# pic16f1829_ads1232_ads1220_hx711.net
KiCad netlist of a schematic drawn in EAGLE
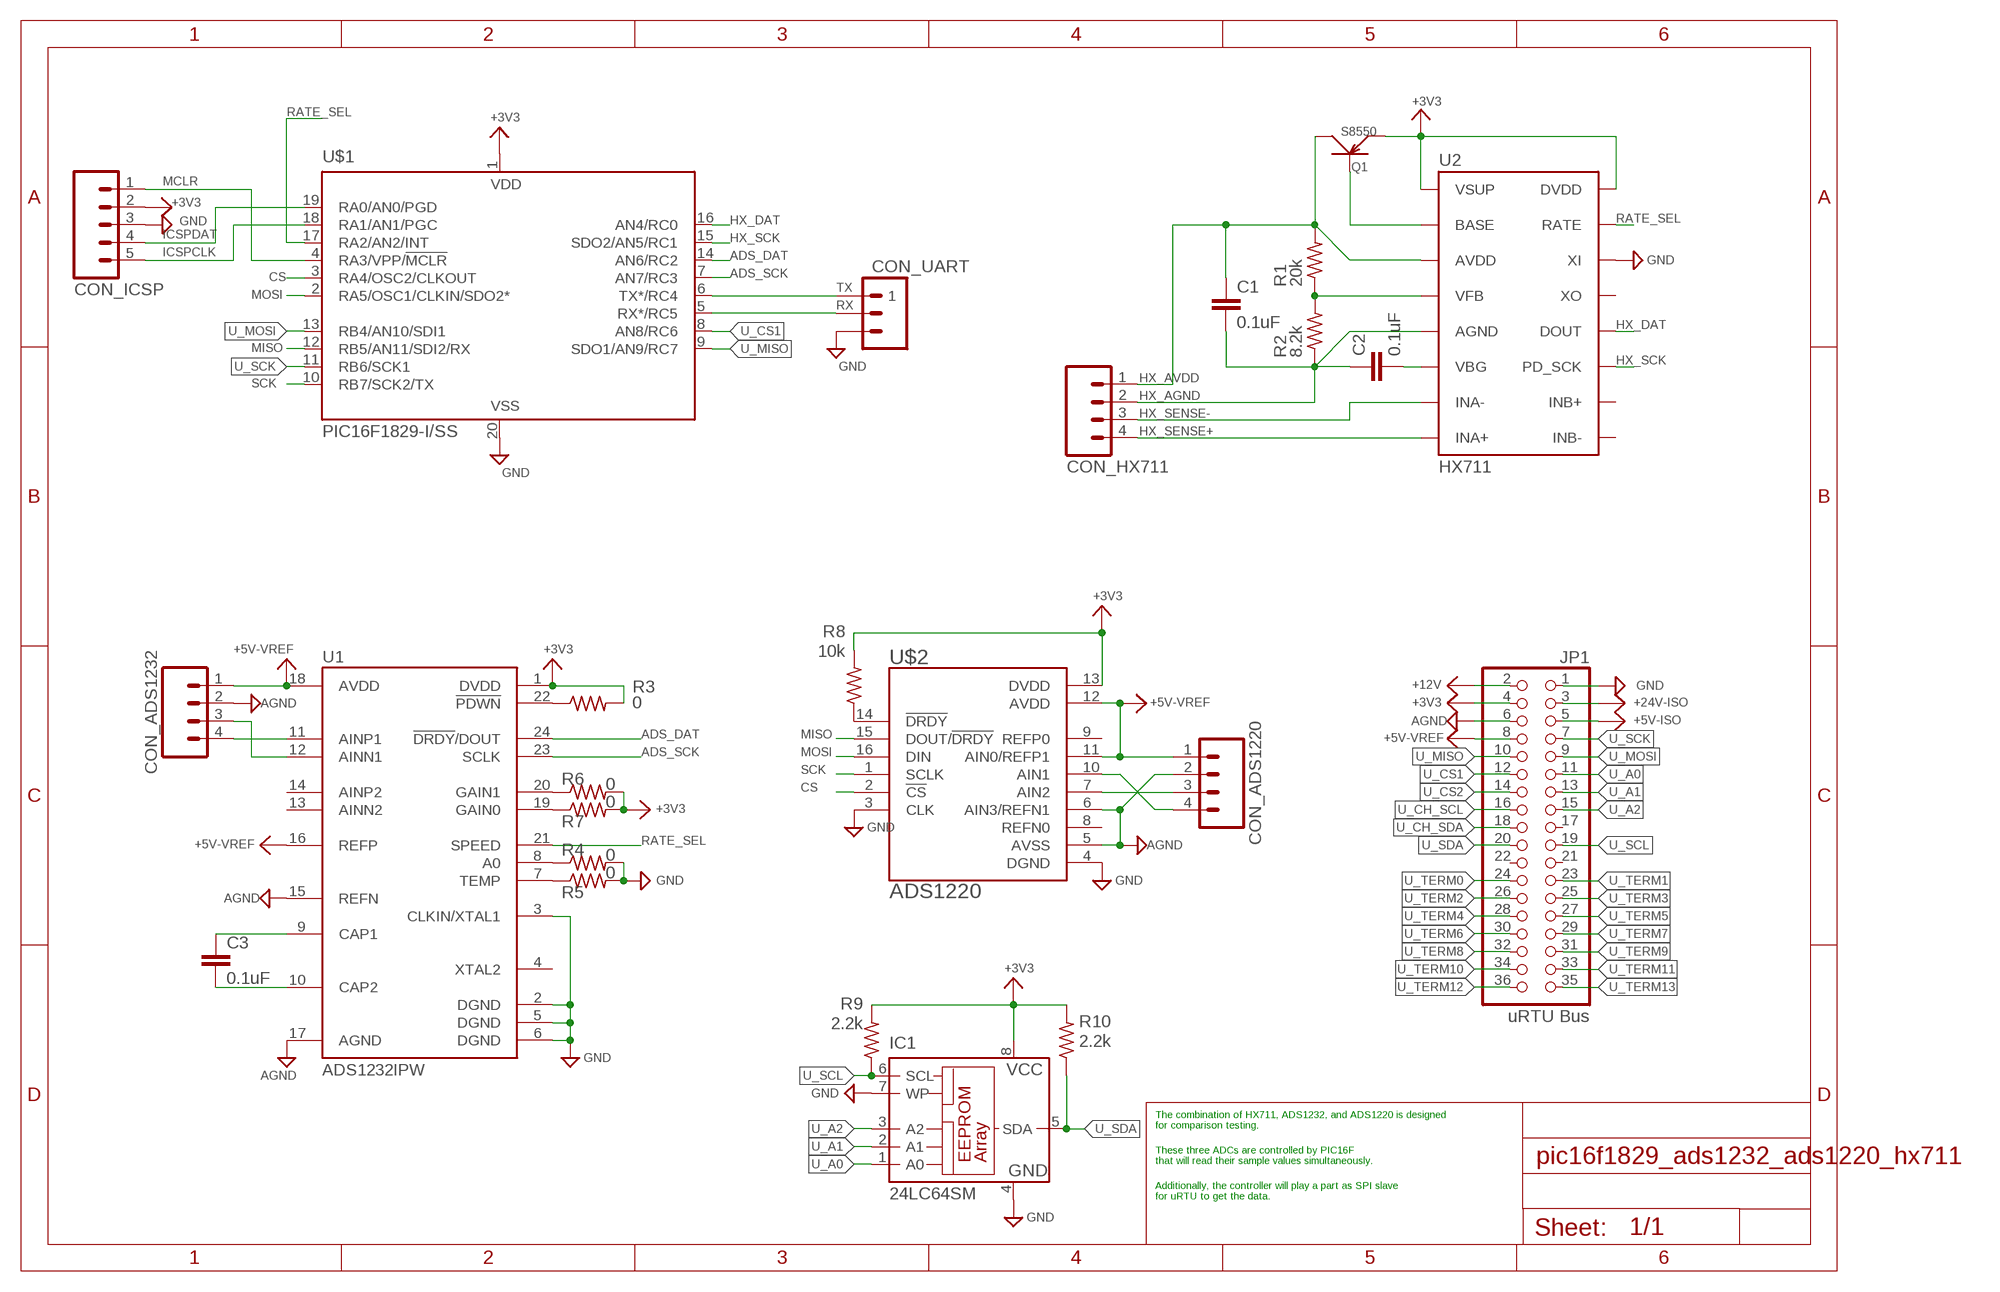
[diagram p0: schematic, sheet 1]

(export (version "E")
  (design (tool "Eeschema 10.0.6"))
  (components
    (comp (ref "C1")
      (value "0.1uF")
      (footprint "eagle-import:RCL_C0805")
      (libsource (lib "eagle-import") (part "RCL_C-EUC0805"))
    )
    (comp (ref "C2")
      (value "0.1uF")
      (footprint "eagle-import:RCL_C0805")
      (libsource (lib "eagle-import") (part "RCL_C-EUC0805"))
    )
    (comp (ref "C3")
      (value "0.1uF")
      (footprint "eagle-import:RCL_C0805")
      (libsource (lib "eagle-import") (part "RCL_C-EUC0805"))
    )
    (comp (ref "CON_ADS1220")
      (value "M04PTH")
      (footprint "eagle-import:1X04")
      (libsource (lib "eagle-import") (part "M04PTH"))
    )
    (comp (ref "CON_ADS1232")
      (value "M04PTH")
      (footprint "eagle-import:1X04")
      (libsource (lib "eagle-import") (part "M04PTH"))
    )
    (comp (ref "CON_HX711")
      (value "M04PTH")
      (footprint "eagle-import:1X04")
      (libsource (lib "eagle-import") (part "M04PTH"))
    )
    (comp (ref "CON_ICSP")
      (value "M05")
      (footprint "eagle-import:1X05")
      (libsource (lib "eagle-import") (part "M05"))
    )
    (comp (ref "CON_UART")
      (value "M03")
      (footprint "eagle-import:1X03")
      (libsource (lib "eagle-import") (part "M03"))
    )
    (comp (ref "IC1")
      (value "24LC64SM")
      (footprint "eagle-import:SO-08M")
      (fields (field (name "MF") "MICROCHIP") (field (name "MPN") "24LC64T-I/SN"))
      (libsource (lib "eagle-import") (part "24SMLC64"))
    )
    (comp (ref "JP1")
      (value "uRTU Bus")
      (footprint "eagle-import:2X18")
      (libsource (lib "eagle-import") (part "PINHD-2X18"))
    )
    (comp (ref "Q1")
      (value "S8550")
      (footprint "eagle-import:SOT-23")
      (libsource (lib "eagle-import") (part "SMD-TRANSISTORS-PNP-25V-500MA-S8550(SOT-23)"))
    )
    (comp (ref "R1")
      (value "20k")
      (footprint "eagle-import:RCL_M0805")
      (libsource (lib "eagle-import") (part "RCL_R-USM0805"))
    )
    (comp (ref "R2")
      (value "8.2k")
      (footprint "eagle-import:RCL_M0805")
      (libsource (lib "eagle-import") (part "RCL_R-USM0805"))
    )
    (comp (ref "R3")
      (value "0")
      (footprint "eagle-import:RCL_M0805")
      (libsource (lib "eagle-import") (part "RCL_R-USM0805"))
    )
    (comp (ref "R4")
      (value "0")
      (footprint "eagle-import:RCL_M0805")
      (libsource (lib "eagle-import") (part "RCL_R-USM0805"))
    )
    (comp (ref "R5")
      (value "0")
      (footprint "eagle-import:RCL_M0805")
      (libsource (lib "eagle-import") (part "RCL_R-USM0805"))
    )
    (comp (ref "R6")
      (value "0")
      (footprint "eagle-import:RCL_M0805")
      (libsource (lib "eagle-import") (part "RCL_R-USM0805"))
    )
    (comp (ref "R7")
      (value "0")
      (footprint "eagle-import:RCL_M0805")
      (libsource (lib "eagle-import") (part "RCL_R-USM0805"))
    )
    (comp (ref "R8")
      (value "10k")
      (footprint "eagle-import:RCL_M0805")
      (libsource (lib "eagle-import") (part "RCL_R-USM0805"))
    )
    (comp (ref "R9")
      (value "2.2k")
      (footprint "eagle-import:RCL_M0805")
      (libsource (lib "eagle-import") (part "RCL_R-USM0805"))
    )
    (comp (ref "R10")
      (value "2.2k")
      (footprint "eagle-import:RCL_M0805")
      (libsource (lib "eagle-import") (part "RCL_R-USM0805"))
    )
    (comp (ref "U$1")
      (value "PIC16F1829-I/SS")
      (footprint "eagle-import:SSOP20")
      (libsource (lib "eagle-import") (part "PIC16F1829"))
    )
    (comp (ref "U$2")
      (value "ADS1220")
      (footprint "eagle-import:TSSOP-16")
      (libsource (lib "eagle-import") (part "ADS1220"))
    )
    (comp (ref "U1")
      (value "ADS1232IPW")
      (footprint "eagle-import:TSSOP24")
      (libsource (lib "eagle-import") (part "ADS1232PWI"))
    )
    (comp (ref "U2")
      (value "HX711")
      (footprint "eagle-import:SO16")
      (libsource (lib "eagle-import") (part "HX711"))
    )
  )
  (nets
    (net (code "1") (name "+3V3") (class "Default")
      (node (ref "CON_ICSP") (pin "2") (pinfunction "2_2") (pintype "passive"))
      (node (ref "IC1") (pin "8") (pinfunction "VCC_8") (pintype "power_in"))
      (node (ref "JP1") (pin "4") (pinfunction "4_4") (pintype "passive"))
      (node (ref "Q1") (pin "2") (pinfunction "E_2") (pintype "passive"))
      (node (ref "R10") (pin "2") (pinfunction "2_2") (pintype "passive"))
      (node (ref "R3") (pin "2") (pinfunction "2_2") (pintype "passive"))
      (node (ref "R6") (pin "2") (pinfunction "2_2") (pintype "passive"))
      (node (ref "R7") (pin "2") (pinfunction "2_2") (pintype "passive"))
      (node (ref "R8") (pin "2") (pinfunction "2_2") (pintype "passive"))
      (node (ref "R9") (pin "2") (pinfunction "2_2") (pintype "passive"))
      (node (ref "U$1") (pin "1") (pinfunction "VDD_1") (pintype "power_in"))
      (node (ref "U$2") (pin "13") (pinfunction "DVDD_13") (pintype "bidirectional"))
      (node (ref "U1") (pin "1") (pinfunction "DVDD_1") (pintype "power_in"))
      (node (ref "U2") (pin "1") (pinfunction "VSUP_1") (pintype "bidirectional"))
      (node (ref "U2") (pin "16") (pinfunction "DVDD_16") (pintype "bidirectional"))
    )
    (net (code "2") (name "+5V-ISO") (class "Default")
      (node (ref "JP1") (pin "5") (pinfunction "5_5") (pintype "passive"))
    )
    (net (code "3") (name "+5V-VREF") (class "Default")
      (node (ref "CON_ADS1220") (pin "1") (pinfunction "1_1") (pintype "passive"))
      (node (ref "CON_ADS1232") (pin "1") (pinfunction "1_1") (pintype "passive"))
      (node (ref "JP1") (pin "8") (pinfunction "8_8") (pintype "passive"))
      (node (ref "U$2") (pin "11") (pinfunction "AIN0/REFP1_11") (pintype "bidirectional"))
      (node (ref "U$2") (pin "12") (pinfunction "AVDD_12") (pintype "bidirectional"))
      (node (ref "U1") (pin "16") (pinfunction "REFP_16") (pintype "input"))
      (node (ref "U1") (pin "18") (pinfunction "AVDD_18") (pintype "power_in"))
    )
    (net (code "4") (name "+12V") (class "Default")
      (node (ref "JP1") (pin "2") (pinfunction "2_2") (pintype "passive"))
    )
    (net (code "5") (name "+24V-ISO") (class "Default")
      (node (ref "JP1") (pin "3") (pinfunction "3_3") (pintype "passive"))
    )
    (net (code "6") (name "/ADS_DAT") (class "Default")
      (node (ref "U$1") (pin "14") (pinfunction "AN6/RC2_14") (pintype "bidirectional"))
      (node (ref "U1") (pin "24") (pinfunction "~{DRDY}/DOUT_24") (pintype "output"))
    )
    (net (code "7") (name "/ADS_SCK") (class "Default")
      (node (ref "U$1") (pin "7") (pinfunction "AN7/RC3_7") (pintype "bidirectional"))
      (node (ref "U1") (pin "23") (pinfunction "SCLK_23") (pintype "input"))
    )
    (net (code "8") (name "/CS") (class "Default")
      (node (ref "U$1") (pin "3") (pinfunction "RA4/OSC2/CLKOUT_3") (pintype "bidirectional"))
      (node (ref "U$2") (pin "2") (pinfunction "~{CS}_2") (pintype "bidirectional"))
    )
    (net (code "9") (name "/HX_AGND") (class "Default")
      (node (ref "C1") (pin "2") (pinfunction "2_2") (pintype "passive"))
      (node (ref "C2") (pin "1") (pinfunction "1_1") (pintype "passive"))
      (node (ref "CON_HX711") (pin "2") (pinfunction "2_2") (pintype "passive"))
      (node (ref "R2") (pin "1") (pinfunction "1_1") (pintype "passive"))
      (node (ref "U2") (pin "5") (pinfunction "AGND_5") (pintype "bidirectional"))
    )
    (net (code "10") (name "/HX_AVDD") (class "Default")
      (node (ref "C1") (pin "1") (pinfunction "1_1") (pintype "passive"))
      (node (ref "CON_HX711") (pin "1") (pinfunction "1_1") (pintype "passive"))
      (node (ref "Q1") (pin "3") (pinfunction "C_3") (pintype "passive"))
      (node (ref "R1") (pin "2") (pinfunction "2_2") (pintype "passive"))
      (node (ref "U2") (pin "3") (pinfunction "AVDD_3") (pintype "bidirectional"))
    )
    (net (code "11") (name "/HX_DAT") (class "Default")
      (node (ref "U$1") (pin "16") (pinfunction "AN4/RC0_16") (pintype "bidirectional"))
      (node (ref "U2") (pin "12") (pinfunction "DOUT_12") (pintype "bidirectional"))
    )
    (net (code "12") (name "/HX_SCK") (class "Default")
      (node (ref "U$1") (pin "15") (pinfunction "SDO2/AN5/RC1_15") (pintype "bidirectional"))
      (node (ref "U2") (pin "11") (pinfunction "PD_SCK_11") (pintype "bidirectional"))
    )
    (net (code "13") (name "/HX_SENSE+") (class "Default")
      (node (ref "CON_HX711") (pin "4") (pinfunction "4_4") (pintype "passive"))
      (node (ref "U2") (pin "8") (pinfunction "INA+_8") (pintype "bidirectional"))
    )
    (net (code "14") (name "/HX_SENSE-") (class "Default")
      (node (ref "CON_HX711") (pin "3") (pinfunction "3_3") (pintype "passive"))
      (node (ref "U2") (pin "7") (pinfunction "INA-_7") (pintype "bidirectional"))
    )
    (net (code "15") (name "/ICSPCLK") (class "Default")
      (node (ref "CON_ICSP") (pin "5") (pinfunction "5_5") (pintype "passive"))
      (node (ref "U$1") (pin "18") (pinfunction "RA1/AN1/PGC_18") (pintype "bidirectional"))
    )
    (net (code "16") (name "/ICSPDAT") (class "Default")
      (node (ref "CON_ICSP") (pin "4") (pinfunction "4_4") (pintype "passive"))
      (node (ref "U$1") (pin "19") (pinfunction "RA0/AN0/PGD_19") (pintype "bidirectional"))
    )
    (net (code "17") (name "/MCLR") (class "Default")
      (node (ref "CON_ICSP") (pin "1") (pinfunction "1_1") (pintype "passive"))
      (node (ref "U$1") (pin "4") (pinfunction "RA3/VPP/~{MCLR}_4") (pintype "input"))
    )
    (net (code "18") (name "/MISO") (class "Default")
      (node (ref "U$1") (pin "12") (pinfunction "RB5/AN11/SDI2/RX_12") (pintype "bidirectional"))
      (node (ref "U$2") (pin "15") (pinfunction "DOUT/~{DRDY}_15") (pintype "bidirectional"))
    )
    (net (code "19") (name "/MOSI") (class "Default")
      (node (ref "U$1") (pin "2") (pinfunction "RA5/OSC1/CLKIN/SDO2*_2") (pintype "bidirectional"))
      (node (ref "U$2") (pin "16") (pinfunction "DIN_16") (pintype "bidirectional"))
    )
    (net (code "20") (name "/RATE_SEL") (class "Default")
      (node (ref "U$1") (pin "17") (pinfunction "RA2/AN2/INT_17") (pintype "bidirectional"))
      (node (ref "U1") (pin "21") (pinfunction "SPEED_21") (pintype "input"))
      (node (ref "U2") (pin "15") (pinfunction "RATE_15") (pintype "bidirectional"))
    )
    (net (code "21") (name "/RX") (class "Default")
      (node (ref "CON_UART") (pin "2") (pinfunction "2_2") (pintype "passive"))
      (node (ref "U$1") (pin "5") (pinfunction "RX*/RC5_5") (pintype "bidirectional"))
    )
    (net (code "22") (name "/SCK") (class "Default")
      (node (ref "U$1") (pin "10") (pinfunction "RB7/SCK2/TX_10") (pintype "bidirectional"))
      (node (ref "U$2") (pin "1") (pinfunction "SCLK_1") (pintype "bidirectional"))
    )
    (net (code "23") (name "/TX") (class "Default")
      (node (ref "CON_UART") (pin "1") (pinfunction "1_1") (pintype "passive"))
      (node (ref "U$1") (pin "6") (pinfunction "TX*/RC4_6") (pintype "bidirectional"))
    )
    (net (code "24") (name "AGND") (class "Default")
      (node (ref "CON_ADS1220") (pin "2") (pinfunction "2_2") (pintype "passive"))
      (node (ref "CON_ADS1232") (pin "2") (pinfunction "2_2") (pintype "passive"))
      (node (ref "JP1") (pin "6") (pinfunction "6_6") (pintype "passive"))
      (node (ref "U$2") (pin "5") (pinfunction "AVSS_5") (pintype "bidirectional"))
      (node (ref "U$2") (pin "6") (pinfunction "AIN3/REFN1_6") (pintype "bidirectional"))
      (node (ref "U1") (pin "15") (pinfunction "REFN_15") (pintype "input"))
      (node (ref "U1") (pin "17") (pinfunction "AGND_17") (pintype "power_in"))
    )
    (net (code "25") (name "GND") (class "Default")
      (node (ref "CON_ICSP") (pin "3") (pinfunction "3_3") (pintype "passive"))
      (node (ref "CON_UART") (pin "3") (pinfunction "3_3") (pintype "passive"))
      (node (ref "IC1") (pin "4") (pinfunction "GND_4") (pintype "power_in"))
      (node (ref "IC1") (pin "7") (pinfunction "WP_7") (pintype "input"))
      (node (ref "JP1") (pin "1") (pinfunction "1_1") (pintype "passive"))
      (node (ref "R4") (pin "2") (pinfunction "2_2") (pintype "passive"))
      (node (ref "R5") (pin "2") (pinfunction "2_2") (pintype "passive"))
      (node (ref "U$1") (pin "20") (pinfunction "VSS_20") (pintype "power_in"))
      (node (ref "U$2") (pin "3") (pinfunction "CLK_3") (pintype "bidirectional"))
      (node (ref "U$2") (pin "4") (pinfunction "DGND_4") (pintype "bidirectional"))
      (node (ref "U1") (pin "2") (pinfunction "DGND_2") (pintype "power_in"))
      (node (ref "U1") (pin "3") (pinfunction "CLKIN/XTAL1_3") (pintype "passive"))
      (node (ref "U1") (pin "5") (pinfunction "DGND_5") (pintype "power_in"))
      (node (ref "U1") (pin "6") (pinfunction "DGND_6") (pintype "power_in"))
      (node (ref "U2") (pin "14") (pinfunction "XI_14") (pintype "bidirectional"))
    )
    (net (code "26") (name "Net-(Q1-B)") (class "Default")
      (node (ref "Q1") (pin "1") (pinfunction "B_1") (pintype "passive"))
      (node (ref "U2") (pin "2") (pinfunction "BASE_2") (pintype "bidirectional"))
    )
    (net (code "27") (name "Net-(U$2-AIN1)") (class "Default")
      (node (ref "CON_ADS1220") (pin "4") (pinfunction "4_4") (pintype "passive"))
      (node (ref "U$2") (pin "10") (pinfunction "AIN1_10") (pintype "bidirectional"))
    )
    (net (code "28") (name "Net-(U$2-AIN2)") (class "Default")
      (node (ref "CON_ADS1220") (pin "3") (pinfunction "3_3") (pintype "passive"))
      (node (ref "U$2") (pin "7") (pinfunction "AIN2_7") (pintype "bidirectional"))
    )
    (net (code "29") (name "Net-(U$2-~{DRDY})") (class "Default")
      (node (ref "R8") (pin "1") (pinfunction "1_1") (pintype "passive"))
      (node (ref "U$2") (pin "14") (pinfunction "~{DRDY}_14") (pintype "bidirectional"))
    )
    (net (code "30") (name "Net-(U1-A0)") (class "Default")
      (node (ref "R4") (pin "1") (pinfunction "1_1") (pintype "passive"))
      (node (ref "U1") (pin "8") (pinfunction "A0_8") (pintype "input"))
    )
    (net (code "31") (name "Net-(U1-AINN1)") (class "Default")
      (node (ref "CON_ADS1232") (pin "3") (pinfunction "3_3") (pintype "passive"))
      (node (ref "U1") (pin "12") (pinfunction "AINN1_12") (pintype "passive"))
    )
    (net (code "32") (name "Net-(U1-AINP1)") (class "Default")
      (node (ref "CON_ADS1232") (pin "4") (pinfunction "4_4") (pintype "passive"))
      (node (ref "U1") (pin "11") (pinfunction "AINP1_11") (pintype "passive"))
    )
    (net (code "33") (name "Net-(U1-CAP1)") (class "Default")
      (node (ref "C3") (pin "1") (pinfunction "1_1") (pintype "passive"))
      (node (ref "U1") (pin "9") (pinfunction "CAP1_9") (pintype "passive"))
    )
    (net (code "34") (name "Net-(U1-CAP2)") (class "Default")
      (node (ref "C3") (pin "2") (pinfunction "2_2") (pintype "passive"))
      (node (ref "U1") (pin "10") (pinfunction "CAP2_10") (pintype "passive"))
    )
    (net (code "35") (name "Net-(U1-GAIN0)") (class "Default")
      (node (ref "R7") (pin "1") (pinfunction "1_1") (pintype "passive"))
      (node (ref "U1") (pin "19") (pinfunction "GAIN0_19") (pintype "input"))
    )
    (net (code "36") (name "Net-(U1-GAIN1)") (class "Default")
      (node (ref "R6") (pin "1") (pinfunction "1_1") (pintype "passive"))
      (node (ref "U1") (pin "20") (pinfunction "GAIN1_20") (pintype "input"))
    )
    (net (code "37") (name "Net-(U1-TEMP)") (class "Default")
      (node (ref "R5") (pin "1") (pinfunction "1_1") (pintype "passive"))
      (node (ref "U1") (pin "7") (pinfunction "TEMP_7") (pintype "input"))
    )
    (net (code "38") (name "Net-(U1-~{PDWN})") (class "Default")
      (node (ref "R3") (pin "1") (pinfunction "1_1") (pintype "passive"))
      (node (ref "U1") (pin "22") (pinfunction "~{PDWN}_22") (pintype "input"))
    )
    (net (code "39") (name "Net-(U2-VBG)") (class "Default")
      (node (ref "C2") (pin "2") (pinfunction "2_2") (pintype "passive"))
      (node (ref "U2") (pin "6") (pinfunction "VBG_6") (pintype "bidirectional"))
    )
    (net (code "40") (name "Net-(U2-VFB)") (class "Default")
      (node (ref "R1") (pin "1") (pinfunction "1_1") (pintype "passive"))
      (node (ref "R2") (pin "2") (pinfunction "2_2") (pintype "passive"))
      (node (ref "U2") (pin "4") (pinfunction "VFB_4") (pintype "bidirectional"))
    )
    (net (code "41") (name "U_A0") (class "Default")
      (node (ref "IC1") (pin "1") (pinfunction "A0_1") (pintype "input"))
      (node (ref "JP1") (pin "11") (pinfunction "11_11") (pintype "passive"))
    )
    (net (code "42") (name "U_A1") (class "Default")
      (node (ref "IC1") (pin "2") (pinfunction "A1_2") (pintype "input"))
      (node (ref "JP1") (pin "13") (pinfunction "13_13") (pintype "passive"))
    )
    (net (code "43") (name "U_A2") (class "Default")
      (node (ref "IC1") (pin "3") (pinfunction "A2_3") (pintype "input"))
      (node (ref "JP1") (pin "15") (pinfunction "15_15") (pintype "passive"))
    )
    (net (code "44") (name "U_CH_SCL") (class "Default")
      (node (ref "JP1") (pin "16") (pinfunction "16_16") (pintype "passive"))
    )
    (net (code "45") (name "U_CH_SDA") (class "Default")
      (node (ref "JP1") (pin "18") (pinfunction "18_18") (pintype "passive"))
    )
    (net (code "46") (name "U_CS1") (class "Default")
      (node (ref "JP1") (pin "12") (pinfunction "12_12") (pintype "passive"))
      (node (ref "U$1") (pin "8") (pinfunction "AN8/RC6_8") (pintype "bidirectional"))
    )
    (net (code "47") (name "U_CS2") (class "Default")
      (node (ref "JP1") (pin "14") (pinfunction "14_14") (pintype "passive"))
    )
    (net (code "48") (name "U_MISO") (class "Default")
      (node (ref "JP1") (pin "10") (pinfunction "10_10") (pintype "passive"))
      (node (ref "U$1") (pin "9") (pinfunction "SDO1/AN9/RC7_9") (pintype "bidirectional"))
    )
    (net (code "49") (name "U_MOSI") (class "Default")
      (node (ref "JP1") (pin "9") (pinfunction "9_9") (pintype "passive"))
      (node (ref "U$1") (pin "13") (pinfunction "RB4/AN10/SDI1_13") (pintype "bidirectional"))
    )
    (net (code "50") (name "U_SCK") (class "Default")
      (node (ref "JP1") (pin "7") (pinfunction "7_7") (pintype "passive"))
      (node (ref "U$1") (pin "11") (pinfunction "RB6/SCK1_11") (pintype "bidirectional"))
    )
    (net (code "51") (name "U_SCL") (class "Default")
      (node (ref "IC1") (pin "6") (pinfunction "SCL_6") (pintype "input"))
      (node (ref "JP1") (pin "19") (pinfunction "19_19") (pintype "passive"))
      (node (ref "R9") (pin "1") (pinfunction "1_1") (pintype "passive"))
    )
    (net (code "52") (name "U_SDA") (class "Default")
      (node (ref "IC1") (pin "5") (pinfunction "SDA_5") (pintype "bidirectional"))
      (node (ref "JP1") (pin "20") (pinfunction "20_20") (pintype "passive"))
      (node (ref "R10") (pin "1") (pinfunction "1_1") (pintype "passive"))
    )
    (net (code "53") (name "U_TERM0") (class "Default")
      (node (ref "JP1") (pin "24") (pinfunction "24_24") (pintype "passive"))
    )
    (net (code "54") (name "U_TERM1") (class "Default")
      (node (ref "JP1") (pin "23") (pinfunction "23_23") (pintype "passive"))
    )
    (net (code "55") (name "U_TERM2") (class "Default")
      (node (ref "JP1") (pin "26") (pinfunction "26_26") (pintype "passive"))
    )
    (net (code "56") (name "U_TERM3") (class "Default")
      (node (ref "JP1") (pin "25") (pinfunction "25_25") (pintype "passive"))
    )
    (net (code "57") (name "U_TERM4") (class "Default")
      (node (ref "JP1") (pin "28") (pinfunction "28_28") (pintype "passive"))
    )
    (net (code "58") (name "U_TERM5") (class "Default")
      (node (ref "JP1") (pin "27") (pinfunction "27_27") (pintype "passive"))
    )
    (net (code "59") (name "U_TERM6") (class "Default")
      (node (ref "JP1") (pin "30") (pinfunction "30_30") (pintype "passive"))
    )
    (net (code "60") (name "U_TERM7") (class "Default")
      (node (ref "JP1") (pin "29") (pinfunction "29_29") (pintype "passive"))
    )
    (net (code "61") (name "U_TERM8") (class "Default")
      (node (ref "JP1") (pin "32") (pinfunction "32_32") (pintype "passive"))
    )
    (net (code "62") (name "U_TERM9") (class "Default")
      (node (ref "JP1") (pin "31") (pinfunction "31_31") (pintype "passive"))
    )
    (net (code "63") (name "U_TERM10") (class "Default")
      (node (ref "JP1") (pin "34") (pinfunction "34_34") (pintype "passive"))
    )
    (net (code "64") (name "U_TERM11") (class "Default")
      (node (ref "JP1") (pin "33") (pinfunction "33_33") (pintype "passive"))
    )
    (net (code "65") (name "U_TERM12") (class "Default")
      (node (ref "JP1") (pin "36") (pinfunction "36_36") (pintype "passive"))
    )
    (net (code "66") (name "U_TERM13") (class "Default")
      (node (ref "JP1") (pin "35") (pinfunction "35_35") (pintype "passive"))
    )
    (net (code "67") (name "unconnected-(JP1-Pad17)") (class "Default")
      (node (ref "JP1") (pin "17") (pinfunction "17_17") (pintype "passive"))
    )
    (net (code "68") (name "unconnected-(JP1-Pad21)") (class "Default")
      (node (ref "JP1") (pin "21") (pinfunction "21_21") (pintype "passive"))
    )
    (net (code "69") (name "unconnected-(JP1-Pad22)") (class "Default")
      (node (ref "JP1") (pin "22") (pinfunction "22_22") (pintype "passive"))
    )
    (net (code "70") (name "unconnected-(U$2-REFN0-Pad8)") (class "Default")
      (node (ref "U$2") (pin "8") (pinfunction "REFN0_8") (pintype "bidirectional"))
    )
    (net (code "71") (name "unconnected-(U$2-REFP0-Pad9)") (class "Default")
      (node (ref "U$2") (pin "9") (pinfunction "REFP0_9") (pintype "bidirectional"))
    )
    (net (code "72") (name "unconnected-(U1-AINN2-Pad13)") (class "Default")
      (node (ref "U1") (pin "13") (pinfunction "AINN2_13") (pintype "passive"))
    )
    (net (code "73") (name "unconnected-(U1-AINP2-Pad14)") (class "Default")
      (node (ref "U1") (pin "14") (pinfunction "AINP2_14") (pintype "passive"))
    )
    (net (code "74") (name "unconnected-(U1-XTAL2-Pad4)") (class "Default")
      (node (ref "U1") (pin "4") (pinfunction "XTAL2_4") (pintype "passive"))
    )
    (net (code "75") (name "unconnected-(U2-INB+-Pad10)") (class "Default")
      (node (ref "U2") (pin "10") (pinfunction "INB+_10") (pintype "bidirectional"))
    )
    (net (code "76") (name "unconnected-(U2-INB--Pad9)") (class "Default")
      (node (ref "U2") (pin "9") (pinfunction "INB-_9") (pintype "bidirectional"))
    )
    (net (code "77") (name "unconnected-(U2-XO-Pad13)") (class "Default")
      (node (ref "U2") (pin "13") (pinfunction "XO_13") (pintype "bidirectional"))
    )
  )
)
